# NAND_gate.net
KiCad netlist of a schematic drawn in EAGLE
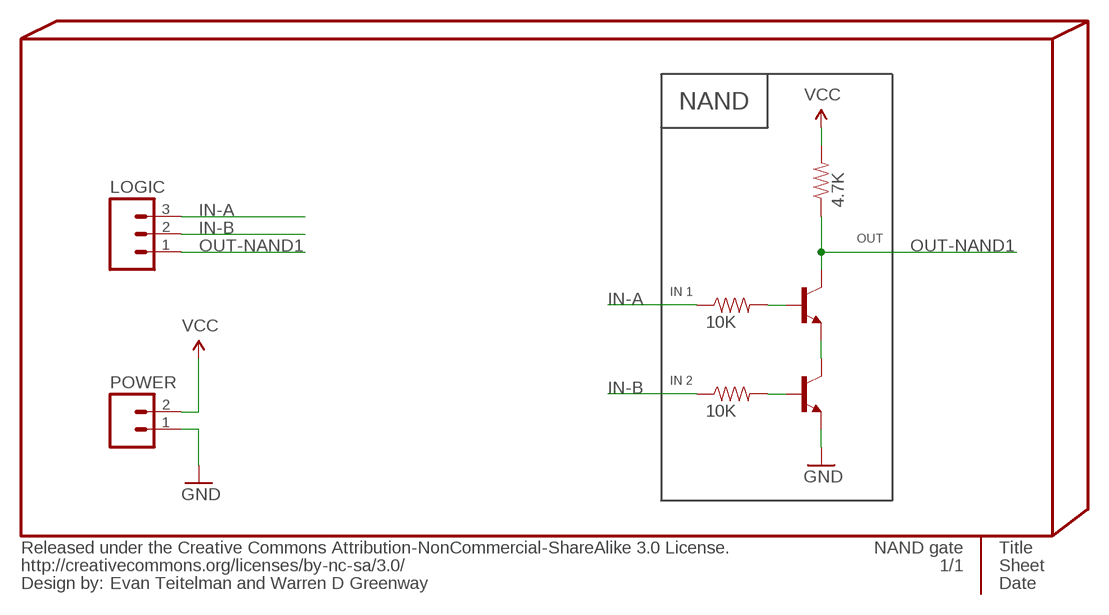
[diagram p0: schematic, sheet 1]

(export (version "E")
  (design (tool "Eeschema 10.0.6"))
  (components
    (comp (ref "INFO4")
      (value "Evan Teitelman and Warren D Greenway")
      (footprint "eagle-import:%CC-NC-SA")
      (libsource (lib "eagle-import") (part "%CC-NC-SA"))
    )
    (comp (ref "LOGIC")
      (value "M03PTH")
      (footprint "eagle-import:1X03")
      (libsource (lib "eagle-import") (part "M03PTH"))
    )
    (comp (ref "POWER")
      (value "M02PTH")
      (footprint "eagle-import:1X02")
      (libsource (lib "eagle-import") (part "M02PTH"))
    )
    (comp (ref "PUR-NAND1")
      (value "4.7K")
      (footprint "eagle-import:0402-RES")
      (libsource (lib "eagle-import") (part "RESISTOR0402-RES"))
    )
    (comp (ref "Q1-NAND1")
      (value "TRANSISTOR_NPNSOT23")
      (footprint "eagle-import:SOT23")
      (libsource (lib "eagle-import") (part "TRANSISTOR_NPNSOT23"))
    )
    (comp (ref "Q2-NAND1")
      (value "TRANSISTOR_NPNSOT23")
      (footprint "eagle-import:SOT23")
      (libsource (lib "eagle-import") (part "TRANSISTOR_NPNSOT23"))
    )
    (comp (ref "R1-NAND1")
      (value "10K")
      (footprint "eagle-import:0402-RES")
      (libsource (lib "eagle-import") (part "RESISTOR0402-RES"))
    )
    (comp (ref "R2-NAND2")
      (value "10K")
      (footprint "eagle-import:0402-RES")
      (libsource (lib "eagle-import") (part "RESISTOR0402-RES"))
    )
  )
  (nets
    (net (code "1") (name "/IN-A") (class "Default")
      (node (ref "LOGIC") (pin "3") (pinfunction "3_3") (pintype "passive"))
      (node (ref "R1-NAND1") (pin "1") (pinfunction "1_1") (pintype "passive"))
    )
    (net (code "2") (name "/IN-B") (class "Default")
      (node (ref "LOGIC") (pin "2") (pinfunction "2_2") (pintype "passive"))
      (node (ref "R2-NAND2") (pin "1") (pinfunction "1_1") (pintype "passive"))
    )
    (net (code "3") (name "/OUT-NAND1") (class "Default")
      (node (ref "LOGIC") (pin "1") (pinfunction "1_1") (pintype "passive"))
      (node (ref "PUR-NAND1") (pin "1") (pinfunction "1_1") (pintype "passive"))
      (node (ref "Q1-NAND1") (pin "3") (pinfunction "C_3") (pintype "passive"))
    )
    (net (code "4") (name "@GND") (class "Default")
      (node (ref "POWER") (pin "1") (pinfunction "1_1") (pintype "passive"))
      (node (ref "Q2-NAND1") (pin "2") (pinfunction "E_2") (pintype "passive"))
    )
    (net (code "5") (name "@VCC") (class "Default")
      (node (ref "POWER") (pin "2") (pinfunction "2_2") (pintype "passive"))
      (node (ref "PUR-NAND1") (pin "2") (pinfunction "2_2") (pintype "passive"))
    )
    (net (code "6") (name "Net-(Q1-NAND1-B)") (class "Default")
      (node (ref "Q1-NAND1") (pin "1") (pinfunction "B_1") (pintype "passive"))
      (node (ref "R1-NAND1") (pin "2") (pinfunction "2_2") (pintype "passive"))
    )
    (net (code "7") (name "Net-(Q1-NAND1-E)") (class "Default")
      (node (ref "Q1-NAND1") (pin "2") (pinfunction "E_2") (pintype "passive"))
      (node (ref "Q2-NAND1") (pin "3") (pinfunction "C_3") (pintype "passive"))
    )
    (net (code "8") (name "Net-(Q2-NAND1-B)") (class "Default")
      (node (ref "Q2-NAND1") (pin "1") (pinfunction "B_1") (pintype "passive"))
      (node (ref "R2-NAND2") (pin "2") (pinfunction "2_2") (pintype "passive"))
    )
  )
)
